# Power.net
KiCad netlist of a schematic drawn in Altium Designer
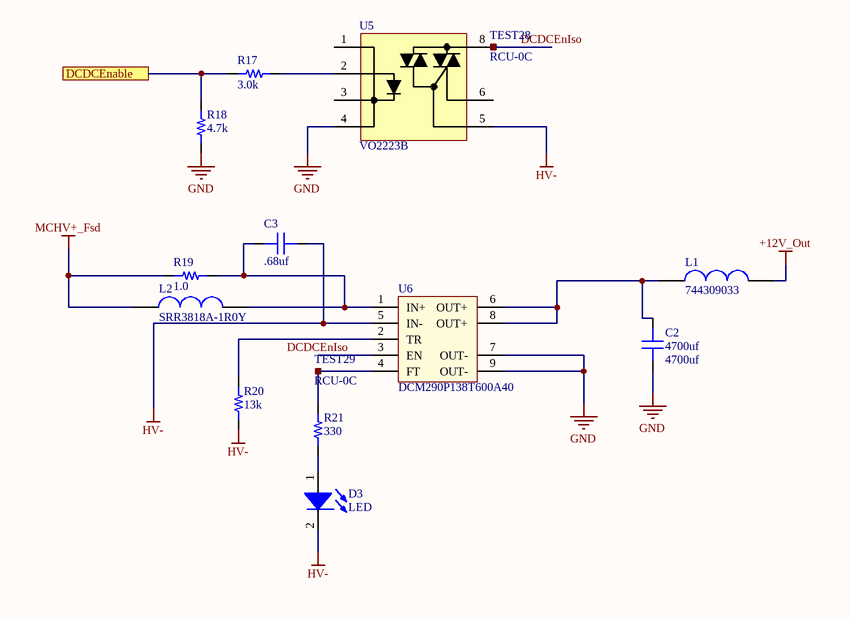
[diagram p0: Power.SchDoc]

(export (version "E")
  (design (tool "Eeschema 10.0.6"))
  (components
    (comp (ref "C2")
      (value "4700uf")
      (footprint "CAP AL TH D16 L7.5 H16.5")
      (fields
        (field (name "ALTIUM_VALUE") "4700uf")
        (field (name "TOLERANCE") "20%")
        (field (name "MFRPARTNO") "UVZ1E472MHD")
        (field (name "CREATED_BY") "Angel Delgado")
      )
      (libsource (lib "Altium-Lib") (part "Capacitor"))
    )
    (comp (ref "C3")
      (value ".68uf")
      (footprint "ECW-FD2W684K-TH-CAP")
      (fields
        (field (name "TOLERANCE") "10%")
        (field (name "MFRPARTNO") "ECW-FD2W684K")
        (field (name "Comment") "HV Cap")
        (field (name "CREATED_BY") "Angel Delgado")
      )
      (libsource (lib "Altium-Lib") (part "Capacitor"))
    )
    (comp (ref "D3") (value "LED") (footprint "0805_LED") (libsource (lib "Altium-Lib") (part "LED")))
    (comp (ref "L1")
      (value "744309033")
      (footprint "744309033")
      (description "330nH wirewound inductor")
      (fields (field (name "CREATED_BY") "Graydon"))
      (libsource (lib "Altium-Lib") (part "744309033"))
    )
    (comp (ref "L2")
      (value "SRR3818A-1R0Y")
      (footprint "SRR3818A-1R0Y")
      (description "1uH fixed inductor")
      (fields (field (name "CREATED_BY") "Graydon"))
      (libsource (lib "Altium-Lib") (part "SRR3818A-1R0Y"))
    )
    (comp (ref "R17")
      (value "3.0k")
      (footprint "RES 0603/1608")
      (fields
        (field (name "TOLERANCE") "1%")
        (field (name "POWER") "1/10W")
        (field (name "Comment") "Resistor 3.0k 0603 1/10W 1%")
        (field (name "CREATED_BY") "Nick Mah")
      )
      (libsource (lib "Altium-Lib") (part "Resistor"))
    )
    (comp (ref "R18")
      (value "4.7k")
      (footprint "RES 0603/1608")
      (fields
        (field (name "TOLERANCE") "1%")
        (field (name "POWER") "1/10W")
        (field (name "Comment") "Resistor 4.7k 0603 1/10W 1%")
        (field (name "CREATED_BY") "Nick Mah")
      )
      (libsource (lib "Altium-Lib") (part "Resistor"))
    )
    (comp (ref "R19")
      (value "1.0")
      (footprint "RES 0603/1608")
      (fields
        (field (name "TOLERANCE") "1%")
        (field (name "POWER") "1/10W")
        (field (name "Comment") "Resistor 1.0 0603 1/10W 1%")
        (field (name "CREATED_BY") "Nick Mah")
      )
      (libsource (lib "Altium-Lib") (part "Resistor"))
    )
    (comp (ref "R20")
      (value "13k")
      (footprint "RES 0603/1608")
      (fields
        (field (name "TOLERANCE") "1%")
        (field (name "POWER") "1/10W")
        (field (name "Comment") "Resistor 13k 0603 1/10W 1%")
        (field (name "CREATED_BY") "Nick Mah")
      )
      (libsource (lib "Altium-Lib") (part "Resistor"))
    )
    (comp (ref "R21")
      (value "330")
      (footprint "RES 0603/1608")
      (fields
        (field (name "TOLERANCE") "1%")
        (field (name "POWER") "1/10W")
        (field (name "Comment") "Resistor 330 0603 1/10W 1%")
        (field (name "CREATED_BY") "Nick Mah")
      )
      (libsource (lib "Altium-Lib") (part "Resistor"))
    )
    (comp (ref "TEST28")
      (value "RCU-0C")
      (footprint "RCU-0C")
      (description "Test point")
      (fields (field (name "CREATED_BY") "Graydon") (field (name "UPDATED_BY") "Null"))
      (libsource (lib "Altium-Lib") (part "RCU-0C"))
    )
    (comp (ref "TEST29")
      (value "RCU-0C")
      (footprint "RCU-0C")
      (description "Test point")
      (fields (field (name "CREATED_BY") "Graydon") (field (name "UPDATED_BY") "Null"))
      (libsource (lib "Altium-Lib") (part "RCU-0C"))
    )
    (comp (ref "U5")
      (value "VO2223B")
      (footprint "Option 7")
      (description "Optocoupler, Power Phototriac")
      (libsource (lib "Altium-Lib") (part "VO2223B"))
    )
    (comp (ref "U6")
      (value "DCM290P138T600A40")
      (footprint "DCM290P138T600A40")
      (description "Vicor DC/DC converter")
      (fields (field (name "CREATED_BY") "Graydon"))
      (libsource (lib "Altium-Lib") (part "DCM290P138T600A40"))
    )
  )
  (nets
    (net (code "1") (name "+12V_Out") (class "Default")
      (node (ref "L1") (pin "2") (pinfunction "2_2") (pintype "power_in"))
    )
    (net (code "2") (name "/DCDCEnIso") (class "Default")
      (node (ref "TEST28") (pin "1") (pintype "passive"))
      (node (ref "U5") (pin "8") (pintype "power_in"))
      (node (ref "U6") (pin "3") (pinfunction "EN_3") (pintype "power_in"))
    )
    (net (code "3") (name "/DCDCEnable") (class "Default")
      (node (ref "R17") (pin "1") (pinfunction "1_1") (pintype "passive"))
      (node (ref "R18") (pin "2") (pinfunction "2_2") (pintype "passive"))
    )
    (net (code "4") (name "GND") (class "Default")
      (node (ref "C2") (pin "2") (pinfunction "2_2") (pintype "passive"))
      (node (ref "R18") (pin "1") (pinfunction "1_1") (pintype "passive"))
      (node (ref "U5") (pin "4") (pintype "power_in"))
      (node (ref "U6") (pin "7") (pinfunction "OUT-_7") (pintype "power_in"))
      (node (ref "U6") (pin "9") (pinfunction "OUT-_9") (pintype "power_in"))
    )
    (net (code "5") (name "HV-") (class "Default")
      (node (ref "C3") (pin "1") (pinfunction "1_1") (pintype "passive"))
      (node (ref "D3") (pin "2") (pinfunction "K_2") (pintype "passive"))
      (node (ref "R20") (pin "1") (pinfunction "1_1") (pintype "passive"))
      (node (ref "U5") (pin "5") (pintype "power_in"))
      (node (ref "U6") (pin "5") (pinfunction "IN-_5") (pintype "power_in"))
    )
    (net (code "6") (name "MCHV+_Fsd") (class "Default")
      (node (ref "L2") (pin "1") (pintype "power_in"))
      (node (ref "R19") (pin "1") (pinfunction "1_1") (pintype "passive"))
    )
    (net (code "7") (name "Net-(C2-Pad1)") (class "Default")
      (node (ref "C2") (pin "1") (pinfunction "1_1") (pintype "passive"))
      (node (ref "L1") (pin "1") (pintype "power_in"))
      (node (ref "U6") (pin "6") (pinfunction "OUT+_6") (pintype "power_in"))
      (node (ref "U6") (pin "8") (pinfunction "OUT+_8") (pintype "power_in"))
    )
    (net (code "8") (name "Net-(D3-A)") (class "Default")
      (node (ref "D3") (pin "1") (pinfunction "A_1") (pintype "passive"))
      (node (ref "R21") (pin "1") (pinfunction "1_1") (pintype "passive"))
    )
    (net (code "9") (name "Net-(R17-Pad2)") (class "Default")
      (node (ref "R17") (pin "2") (pinfunction "2_2") (pintype "passive"))
      (node (ref "U5") (pin "2") (pintype "power_in"))
    )
    (net (code "10") (name "Net-(U6-FT)") (class "Default")
      (node (ref "R21") (pin "2") (pinfunction "2_2") (pintype "passive"))
      (node (ref "TEST29") (pin "1") (pintype "passive"))
      (node (ref "U6") (pin "4") (pinfunction "FT_4") (pintype "power_in"))
    )
    (net (code "11") (name "Net-(U6-IN+)") (class "Default")
      (node (ref "C3") (pin "2") (pinfunction "2_2") (pintype "passive"))
      (node (ref "L2") (pin "2") (pinfunction "2_2") (pintype "power_in"))
      (node (ref "R19") (pin "2") (pinfunction "2_2") (pintype "passive"))
      (node (ref "U6") (pin "1") (pinfunction "IN+_1") (pintype "power_in"))
    )
    (net (code "12") (name "Net-(U6-TR)") (class "Default")
      (node (ref "R20") (pin "2") (pinfunction "2_2") (pintype "passive"))
      (node (ref "U6") (pin "2") (pinfunction "TR_2") (pintype "power_in"))
    )
    (net (code "13") (name "unconnected-(U5-Pad1)") (class "Default")
      (node (ref "U5") (pin "1") (pintype "power_in"))
    )
    (net (code "14") (name "unconnected-(U5-Pad3)") (class "Default")
      (node (ref "U5") (pin "3") (pintype "power_in"))
    )
    (net (code "15") (name "unconnected-(U5-Pad6)") (class "Default")
      (node (ref "U5") (pin "6") (pintype "power_in"))
    )
  )
)
